# 5v_power_supply.net
KiCad netlist of a schematic drawn in EAGLE
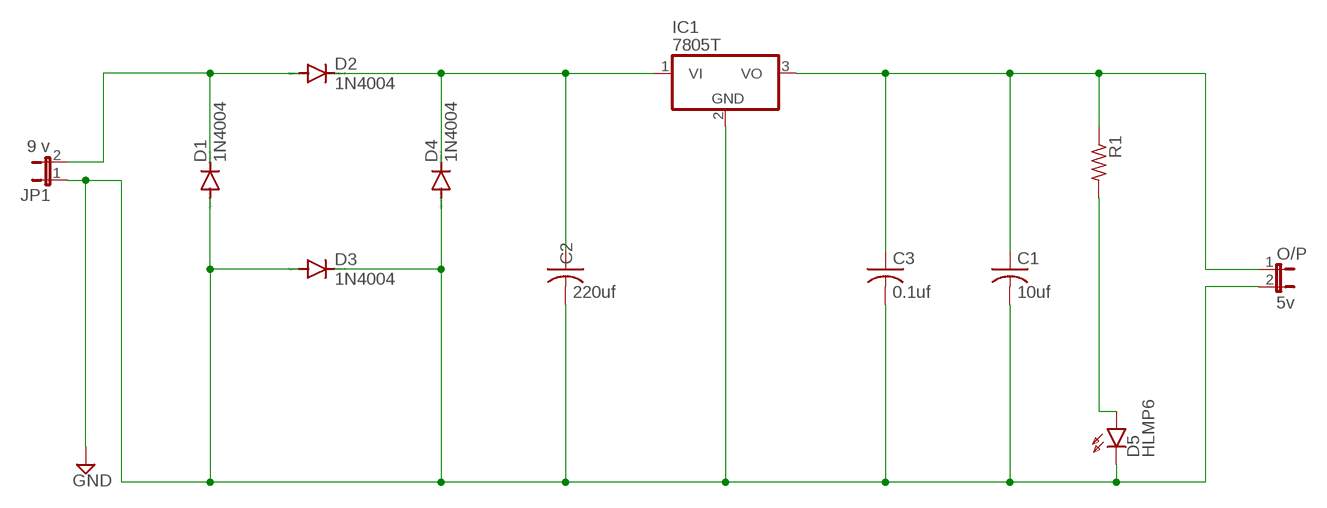
[diagram p0: schematic, sheet 1]

(export (version "E")
  (design (tool "Eeschema 10.0.6"))
  (components
    (comp (ref "C1")
      (value "10uf")
      (footprint "eagle-import:C025-024X044")
      (libsource (lib "eagle-import") (part "C-US025-024X044"))
    )
    (comp (ref "C2")
      (value "220uf")
      (footprint "eagle-import:C025-024X044")
      (libsource (lib "eagle-import") (part "C-US025-024X044"))
    )
    (comp (ref "C3")
      (value "0.1uf")
      (footprint "eagle-import:C025-024X044")
      (libsource (lib "eagle-import") (part "C-US025-024X044"))
    )
    (comp (ref "D1")
      (value "1N4004")
      (footprint "eagle-import:DO41-10")
      (libsource (lib "eagle-import") (part "1N4004"))
    )
    (comp (ref "D2")
      (value "1N4004")
      (footprint "eagle-import:DO41-10")
      (libsource (lib "eagle-import") (part "1N4004"))
    )
    (comp (ref "D3")
      (value "1N4004")
      (footprint "eagle-import:DO41-10")
      (libsource (lib "eagle-import") (part "1N4004"))
    )
    (comp (ref "D4")
      (value "1N4004")
      (footprint "eagle-import:DO41-10")
      (libsource (lib "eagle-import") (part "1N4004"))
    )
    (comp (ref "D5")
      (value "HLMP6")
      (footprint "eagle-import:HLMP6")
      (fields (field (name "MF") "AGILENT TECHNOLOGIES") (field (name "MPN") "HLMP-6500"))
      (libsource (lib "eagle-import") (part "HLMP6"))
    )
    (comp (ref "IC1")
      (value "7805T")
      (footprint "eagle-import:TO220H")
      (libsource (lib "eagle-import") (part "78T05"))
    )
    (comp (ref "JP1")
      (value "9 v")
      (footprint "eagle-import:JP1")
      (libsource (lib "eagle-import") (part "JP1E"))
    )
    (comp (ref "O/P")
      (value "5v")
      (footprint "eagle-import:JP1")
      (libsource (lib "eagle-import") (part "JP1E"))
    )
    (comp (ref "R1")
      (value "R-US_0204/2V")
      (footprint "eagle-import:0204V")
      (libsource (lib "eagle-import") (part "R-US_0204/2V"))
    )
  )
  (nets
    (net (code "1") (name "GND") (class "Default")
      (node (ref "C1") (pin "2") (pinfunction "2_2") (pintype "passive"))
      (node (ref "C2") (pin "2") (pinfunction "2_2") (pintype "passive"))
      (node (ref "C3") (pin "2") (pinfunction "2_2") (pintype "passive"))
      (node (ref "D1") (pin "A") (pinfunction "A_A") (pintype "passive"))
      (node (ref "D3") (pin "A") (pinfunction "A_A") (pintype "passive"))
      (node (ref "D3") (pin "C") (pinfunction "C_C") (pintype "passive"))
      (node (ref "D4") (pin "A") (pinfunction "A_A") (pintype "passive"))
      (node (ref "D5") (pin "K") (pinfunction "K_K") (pintype "passive"))
      (node (ref "IC1") (pin "2") (pinfunction "GND_2") (pintype "passive"))
      (node (ref "JP1") (pin "1") (pinfunction "1_1") (pintype "passive"))
      (node (ref "O/P") (pin "2") (pinfunction "2_2") (pintype "passive"))
    )
    (net (code "2") (name "Net-(D1-PadC)") (class "Default")
      (node (ref "D1") (pin "C") (pinfunction "C_C") (pintype "passive"))
      (node (ref "D2") (pin "A") (pinfunction "A_A") (pintype "passive"))
      (node (ref "JP1") (pin "2") (pinfunction "2_2") (pintype "passive"))
    )
    (net (code "3") (name "Net-(D5-PadA)") (class "Default")
      (node (ref "D5") (pin "A") (pinfunction "A_A") (pintype "passive"))
      (node (ref "R1") (pin "2") (pinfunction "2_2") (pintype "passive"))
    )
    (net (code "4") (name "Net-(IC1-VI)") (class "Default")
      (node (ref "C2") (pin "1") (pinfunction "1_1") (pintype "passive"))
      (node (ref "D2") (pin "C") (pinfunction "C_C") (pintype "passive"))
      (node (ref "D4") (pin "C") (pinfunction "C_C") (pintype "passive"))
      (node (ref "IC1") (pin "1") (pinfunction "VI_1") (pintype "input"))
    )
    (net (code "5") (name "Net-(IC1-VO)") (class "Default")
      (node (ref "C1") (pin "1") (pinfunction "1_1") (pintype "passive"))
      (node (ref "C3") (pin "1") (pinfunction "1_1") (pintype "passive"))
      (node (ref "IC1") (pin "3") (pinfunction "VO_3") (pintype "passive"))
      (node (ref "O/P") (pin "1") (pinfunction "1_1") (pintype "passive"))
      (node (ref "R1") (pin "1") (pinfunction "1_1") (pintype "passive"))
    )
  )
)
